# 1-Schematic_copilot.net
KiCad netlist of a schematic drawn in EasyEDA
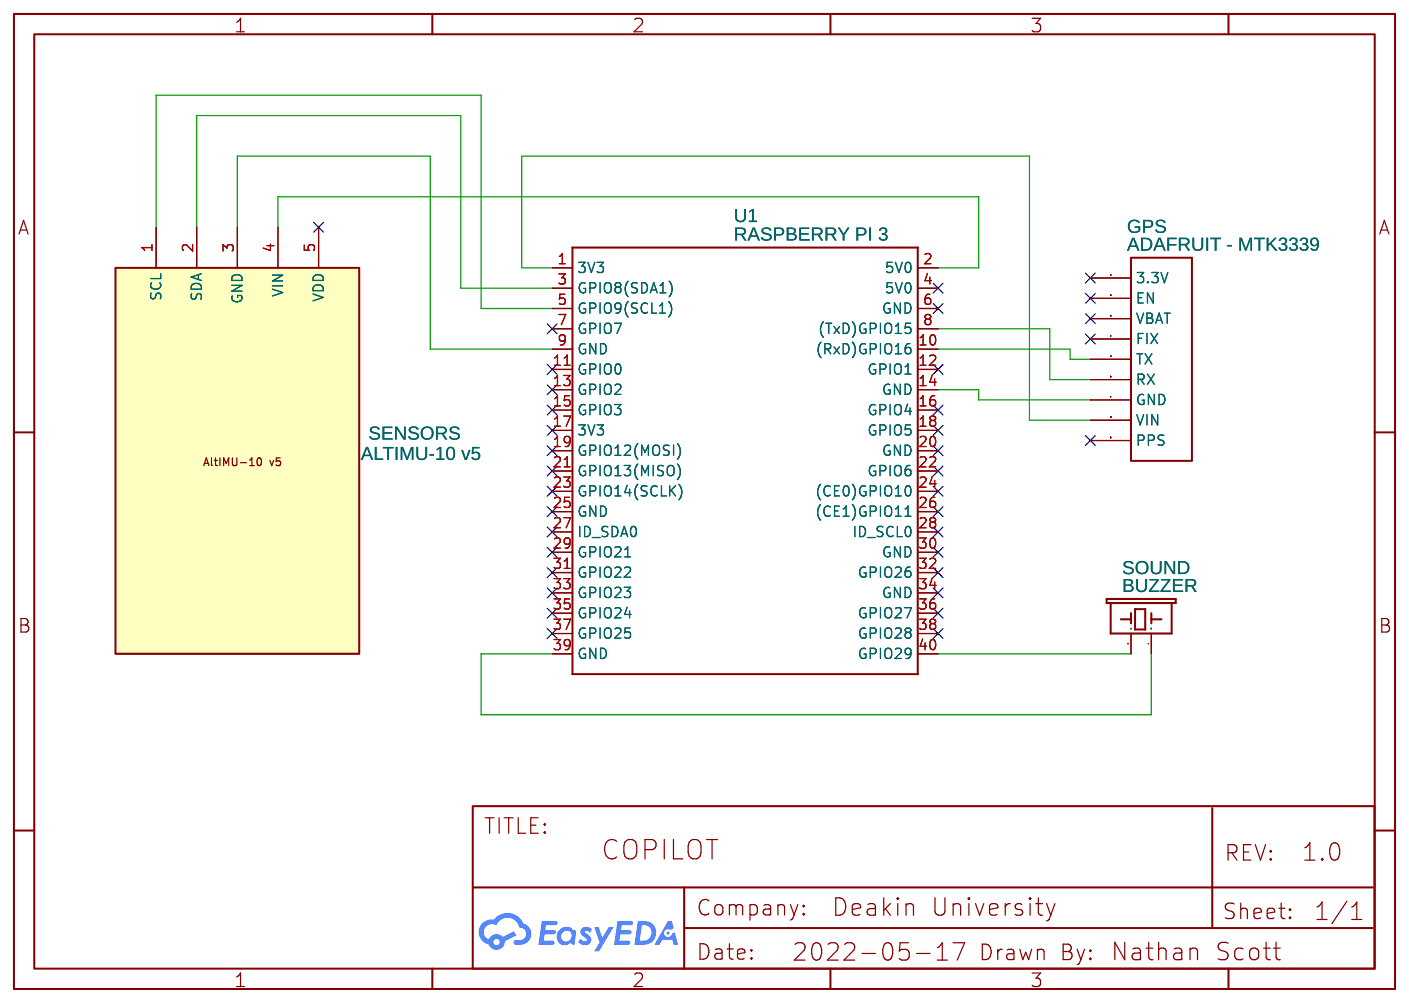
[diagram p0: copilot_sim]
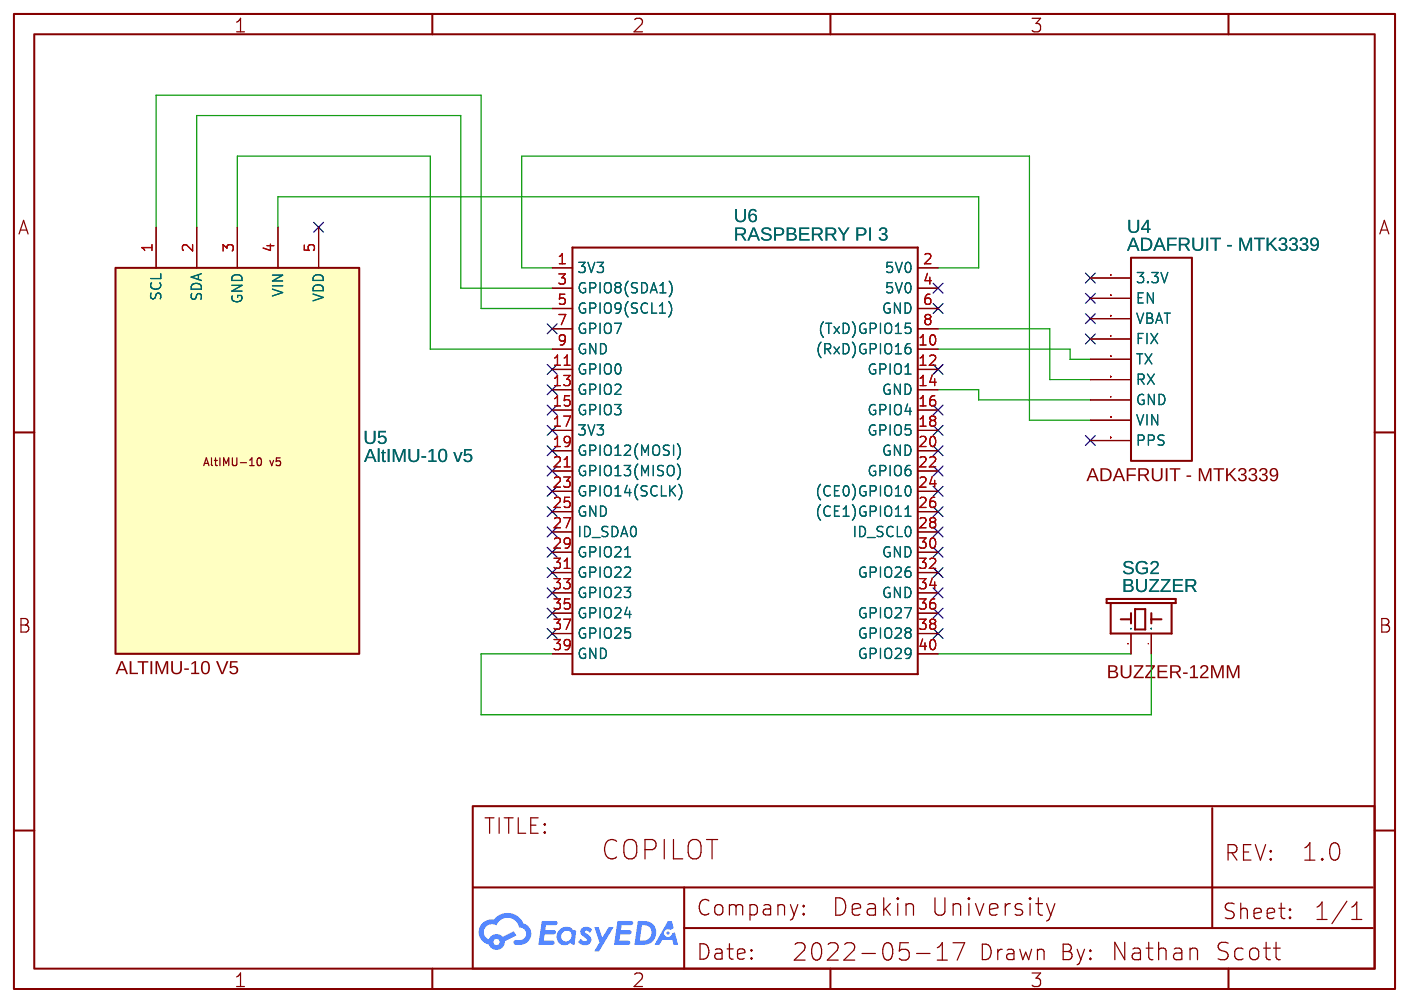
[diagram p1: copilot_sch]

(export (version "E")
  (design (tool "Eeschema 10.0.6"))
  (components
    (comp (ref "GPS") (value "ADAFRUIT - MTK3339") (libsource (lib "") (part "ADAFRUIT - MTK3339")))
    (comp (ref "SENSORS") (value "ALTIMU-10 v5") (libsource (lib "") (part "AltIMU-10 v5")))
    (comp (ref "SOUND") (value "BUZZER") (libsource (lib "") (part "BUZZER")))
    (comp (ref "U1")
      (value "RASPBERRY PI 3")
      (fields (field (name "BOM_Supplier Part") "RaspberryPi 3"))
      (libsource (lib "") (part "RASPBERRY PI 3"))
    )
    (comp (ref "SG2") (value "BUZZER") (libsource (lib "") (part "BUZZER")))
    (comp (ref "U4") (value "ADAFRUIT - MTK3339") (libsource (lib "") (part "ADAFRUIT - MTK3339")))
    (comp (ref "U5") (value "AltIMU-10 v5") (libsource (lib "") (part "AltIMU-10 v5")))
    (comp (ref "U6")
      (value "RASPBERRY PI 3")
      (fields (field (name "BOM_Supplier Part") "RaspberryPi 3"))
      (libsource (lib "") (part "RASPBERRY PI 3"))
    )
  )
  (nets
    (net (code "1") (name "Net-(GPS-GND)") (class "Default")
      (node (ref "GPS") (pin "7") (pinfunction "GND_7") (pintype "unspecified"))
      (node (ref "U1") (pin "14") (pinfunction "GND_14") (pintype "unspecified"))
    )
    (net (code "2") (name "Net-(GPS-RX)") (class "Default")
      (node (ref "GPS") (pin "6") (pinfunction "RX_6") (pintype "unspecified"))
      (node (ref "U1") (pin "8") (pinfunction "(TxD)GPIO15_8") (pintype "unspecified"))
    )
    (net (code "3") (name "Net-(GPS-TX)") (class "Default")
      (node (ref "GPS") (pin "5") (pinfunction "TX_5") (pintype "unspecified"))
      (node (ref "U1") (pin "10") (pinfunction "(RxD)GPIO16_10") (pintype "unspecified"))
    )
    (net (code "4") (name "Net-(GPS-VIN)") (class "Default")
      (node (ref "GPS") (pin "8") (pinfunction "VIN_8") (pintype "unspecified"))
      (node (ref "U1") (pin "1") (pinfunction "3V3_1") (pintype "unspecified"))
    )
    (net (code "5") (name "Net-(SENSORS-GND)") (class "Default")
      (node (ref "SENSORS") (pin "3") (pinfunction "GND_3") (pintype "unspecified"))
      (node (ref "U1") (pin "9") (pinfunction "GND_9") (pintype "unspecified"))
    )
    (net (code "6") (name "Net-(SENSORS-SCL)") (class "Default")
      (node (ref "SENSORS") (pin "1") (pinfunction "SCL_1") (pintype "unspecified"))
      (node (ref "U1") (pin "5") (pinfunction "GPIO9(SCL1)_5") (pintype "unspecified"))
    )
    (net (code "7") (name "Net-(SENSORS-SDA)") (class "Default")
      (node (ref "SENSORS") (pin "2") (pinfunction "SDA_2") (pintype "unspecified"))
      (node (ref "U1") (pin "3") (pinfunction "GPIO8(SDA1)_3") (pintype "unspecified"))
    )
    (net (code "8") (name "Net-(SENSORS-VIN)") (class "Default")
      (node (ref "SENSORS") (pin "4") (pinfunction "VIN_4") (pintype "unspecified"))
      (node (ref "U1") (pin "2") (pinfunction "5V0_2") (pintype "unspecified"))
    )
    (net (code "9") (name "Net-(SG2-1)") (class "Default")
      (node (ref "SG2") (pin "+") (pinfunction "1_+") (pintype "unspecified"))
      (node (ref "U6") (pin "40") (pinfunction "GPIO29_40") (pintype "unspecified"))
    )
    (net (code "10") (name "Net-(SG2-2)") (class "Default")
      (node (ref "SG2") (pin "-") (pinfunction "2_-") (pintype "unspecified"))
      (node (ref "U6") (pin "39") (pinfunction "GND_39") (pintype "unspecified"))
    )
    (net (code "11") (name "Net-(SOUND-1)") (class "Default")
      (node (ref "SOUND") (pin "+") (pinfunction "1_+") (pintype "unspecified"))
      (node (ref "U1") (pin "40") (pinfunction "GPIO29_40") (pintype "unspecified"))
    )
    (net (code "12") (name "Net-(SOUND-2)") (class "Default")
      (node (ref "SOUND") (pin "-") (pinfunction "2_-") (pintype "unspecified"))
      (node (ref "U1") (pin "39") (pinfunction "GND_39") (pintype "unspecified"))
    )
    (net (code "13") (name "Net-(U4-GND)") (class "Default")
      (node (ref "U4") (pin "7") (pinfunction "GND_7") (pintype "unspecified"))
      (node (ref "U6") (pin "14") (pinfunction "GND_14") (pintype "unspecified"))
    )
    (net (code "14") (name "Net-(U4-RX)") (class "Default")
      (node (ref "U4") (pin "6") (pinfunction "RX_6") (pintype "unspecified"))
      (node (ref "U6") (pin "8") (pinfunction "(TxD)GPIO15_8") (pintype "unspecified"))
    )
    (net (code "15") (name "Net-(U4-TX)") (class "Default")
      (node (ref "U4") (pin "5") (pinfunction "TX_5") (pintype "unspecified"))
      (node (ref "U6") (pin "10") (pinfunction "(RxD)GPIO16_10") (pintype "unspecified"))
    )
    (net (code "16") (name "Net-(U4-VIN)") (class "Default")
      (node (ref "U4") (pin "8") (pinfunction "VIN_8") (pintype "unspecified"))
      (node (ref "U6") (pin "1") (pinfunction "3V3_1") (pintype "unspecified"))
    )
    (net (code "17") (name "Net-(U5-GND)") (class "Default")
      (node (ref "U5") (pin "3") (pinfunction "GND_3") (pintype "unspecified"))
      (node (ref "U6") (pin "9") (pinfunction "GND_9") (pintype "unspecified"))
    )
    (net (code "18") (name "Net-(U5-SCL)") (class "Default")
      (node (ref "U5") (pin "1") (pinfunction "SCL_1") (pintype "unspecified"))
      (node (ref "U6") (pin "5") (pinfunction "GPIO9(SCL1)_5") (pintype "unspecified"))
    )
    (net (code "19") (name "Net-(U5-SDA)") (class "Default")
      (node (ref "U5") (pin "2") (pinfunction "SDA_2") (pintype "unspecified"))
      (node (ref "U6") (pin "3") (pinfunction "GPIO8(SDA1)_3") (pintype "unspecified"))
    )
    (net (code "20") (name "Net-(U5-VIN)") (class "Default")
      (node (ref "U5") (pin "4") (pinfunction "VIN_4") (pintype "unspecified"))
      (node (ref "U6") (pin "2") (pinfunction "5V0_2") (pintype "unspecified"))
    )
    (net (code "21") (name "unconnected-(GPS-3.3V-Pad1)") (class "Default")
      (node (ref "GPS") (pin "1") (pinfunction "3.3V_1") (pintype "unspecified+no_connect"))
    )
    (net (code "22") (name "unconnected-(GPS-EN-Pad2)") (class "Default")
      (node (ref "GPS") (pin "2") (pinfunction "EN_2") (pintype "unspecified+no_connect"))
    )
    (net (code "23") (name "unconnected-(GPS-FIX-Pad4)") (class "Default")
      (node (ref "GPS") (pin "4") (pinfunction "FIX_4") (pintype "unspecified+no_connect"))
    )
    (net (code "24") (name "unconnected-(GPS-PPS-Pad9)") (class "Default")
      (node (ref "GPS") (pin "9") (pinfunction "PPS_9") (pintype "unspecified+no_connect"))
    )
    (net (code "25") (name "unconnected-(GPS-VBAT-Pad3)") (class "Default")
      (node (ref "GPS") (pin "3") (pinfunction "VBAT_3") (pintype "unspecified+no_connect"))
    )
    (net (code "26") (name "unconnected-(SENSORS-VDD-Pad5)") (class "Default")
      (node (ref "SENSORS") (pin "5") (pinfunction "VDD_5") (pintype "unspecified+no_connect"))
    )
    (net (code "27") (name "unconnected-(U1-(CE0)GPIO10-Pad24)") (class "Default")
      (node (ref "U1") (pin "24") (pinfunction "(CE0)GPIO10_24") (pintype "unspecified+no_connect"))
    )
    (net (code "28") (name "unconnected-(U1-(CE1)GPIO11-Pad26)") (class "Default")
      (node (ref "U1") (pin "26") (pinfunction "(CE1)GPIO11_26") (pintype "unspecified+no_connect"))
    )
    (net (code "29") (name "unconnected-(U1-3V3-Pad17)") (class "Default")
      (node (ref "U1") (pin "17") (pinfunction "3V3_17") (pintype "unspecified+no_connect"))
    )
    (net (code "30") (name "unconnected-(U1-5V0-Pad4)") (class "Default")
      (node (ref "U1") (pin "4") (pinfunction "5V0_4") (pintype "unspecified+no_connect"))
    )
    (net (code "31") (name "unconnected-(U1-GND-Pad6)") (class "Default")
      (node (ref "U1") (pin "6") (pinfunction "GND_6") (pintype "unspecified+no_connect"))
    )
    (net (code "32") (name "unconnected-(U1-GND-Pad20)") (class "Default")
      (node (ref "U1") (pin "20") (pinfunction "GND_20") (pintype "unspecified+no_connect"))
    )
    (net (code "33") (name "unconnected-(U1-GND-Pad25)") (class "Default")
      (node (ref "U1") (pin "25") (pinfunction "GND_25") (pintype "unspecified+no_connect"))
    )
    (net (code "34") (name "unconnected-(U1-GND-Pad30)") (class "Default")
      (node (ref "U1") (pin "30") (pinfunction "GND_30") (pintype "unspecified+no_connect"))
    )
    (net (code "35") (name "unconnected-(U1-GND-Pad34)") (class "Default")
      (node (ref "U1") (pin "34") (pinfunction "GND_34") (pintype "unspecified+no_connect"))
    )
    (net (code "36") (name "unconnected-(U1-GPIO0-Pad11)") (class "Default")
      (node (ref "U1") (pin "11") (pinfunction "GPIO0_11") (pintype "unspecified+no_connect"))
    )
    (net (code "37") (name "unconnected-(U1-GPIO1-Pad12)") (class "Default")
      (node (ref "U1") (pin "12") (pinfunction "GPIO1_12") (pintype "unspecified+no_connect"))
    )
    (net (code "38") (name "unconnected-(U1-GPIO2-Pad13)") (class "Default")
      (node (ref "U1") (pin "13") (pinfunction "GPIO2_13") (pintype "unspecified+no_connect"))
    )
    (net (code "39") (name "unconnected-(U1-GPIO3-Pad15)") (class "Default")
      (node (ref "U1") (pin "15") (pinfunction "GPIO3_15") (pintype "unspecified+no_connect"))
    )
    (net (code "40") (name "unconnected-(U1-GPIO4-Pad16)") (class "Default")
      (node (ref "U1") (pin "16") (pinfunction "GPIO4_16") (pintype "unspecified+no_connect"))
    )
    (net (code "41") (name "unconnected-(U1-GPIO5-Pad18)") (class "Default")
      (node (ref "U1") (pin "18") (pinfunction "GPIO5_18") (pintype "unspecified+no_connect"))
    )
    (net (code "42") (name "unconnected-(U1-GPIO6-Pad22)") (class "Default")
      (node (ref "U1") (pin "22") (pinfunction "GPIO6_22") (pintype "unspecified+no_connect"))
    )
    (net (code "43") (name "unconnected-(U1-GPIO7-Pad7)") (class "Default")
      (node (ref "U1") (pin "7") (pinfunction "GPIO7_7") (pintype "unspecified+no_connect"))
    )
    (net (code "44") (name "unconnected-(U1-GPIO12(MOSI)-Pad19)") (class "Default")
      (node (ref "U1") (pin "19") (pinfunction "GPIO12(MOSI)_19") (pintype "unspecified+no_connect"))
    )
    (net (code "45") (name "unconnected-(U1-GPIO13(MISO)-Pad21)") (class "Default")
      (node (ref "U1") (pin "21") (pinfunction "GPIO13(MISO)_21") (pintype "unspecified+no_connect"))
    )
    (net (code "46") (name "unconnected-(U1-GPIO14(SCLK)-Pad23)") (class "Default")
      (node (ref "U1") (pin "23") (pinfunction "GPIO14(SCLK)_23") (pintype "unspecified+no_connect"))
    )
    (net (code "47") (name "unconnected-(U1-GPIO21-Pad29)") (class "Default")
      (node (ref "U1") (pin "29") (pinfunction "GPIO21_29") (pintype "unspecified+no_connect"))
    )
    (net (code "48") (name "unconnected-(U1-GPIO22-Pad31)") (class "Default")
      (node (ref "U1") (pin "31") (pinfunction "GPIO22_31") (pintype "unspecified+no_connect"))
    )
    (net (code "49") (name "unconnected-(U1-GPIO23-Pad33)") (class "Default")
      (node (ref "U1") (pin "33") (pinfunction "GPIO23_33") (pintype "unspecified+no_connect"))
    )
    (net (code "50") (name "unconnected-(U1-GPIO24-Pad35)") (class "Default")
      (node (ref "U1") (pin "35") (pinfunction "GPIO24_35") (pintype "unspecified+no_connect"))
    )
    (net (code "51") (name "unconnected-(U1-GPIO25-Pad37)") (class "Default")
      (node (ref "U1") (pin "37") (pinfunction "GPIO25_37") (pintype "unspecified+no_connect"))
    )
    (net (code "52") (name "unconnected-(U1-GPIO26-Pad32)") (class "Default")
      (node (ref "U1") (pin "32") (pinfunction "GPIO26_32") (pintype "unspecified+no_connect"))
    )
    (net (code "53") (name "unconnected-(U1-GPIO27-Pad36)") (class "Default")
      (node (ref "U1") (pin "36") (pinfunction "GPIO27_36") (pintype "unspecified+no_connect"))
    )
    (net (code "54") (name "unconnected-(U1-GPIO28-Pad38)") (class "Default")
      (node (ref "U1") (pin "38") (pinfunction "GPIO28_38") (pintype "unspecified+no_connect"))
    )
    (net (code "55") (name "unconnected-(U1-ID_SCL0-Pad28)") (class "Default")
      (node (ref "U1") (pin "28") (pinfunction "ID_SCL0_28") (pintype "unspecified+no_connect"))
    )
    (net (code "56") (name "unconnected-(U1-ID_SDA0-Pad27)") (class "Default")
      (node (ref "U1") (pin "27") (pinfunction "ID_SDA0_27") (pintype "unspecified+no_connect"))
    )
    (net (code "57") (name "unconnected-(U4-3.3V-Pad1)") (class "Default")
      (node (ref "U4") (pin "1") (pinfunction "3.3V_1") (pintype "unspecified+no_connect"))
    )
    (net (code "58") (name "unconnected-(U4-EN-Pad2)") (class "Default")
      (node (ref "U4") (pin "2") (pinfunction "EN_2") (pintype "unspecified+no_connect"))
    )
    (net (code "59") (name "unconnected-(U4-FIX-Pad4)") (class "Default")
      (node (ref "U4") (pin "4") (pinfunction "FIX_4") (pintype "unspecified+no_connect"))
    )
    (net (code "60") (name "unconnected-(U4-PPS-Pad9)") (class "Default")
      (node (ref "U4") (pin "9") (pinfunction "PPS_9") (pintype "unspecified+no_connect"))
    )
    (net (code "61") (name "unconnected-(U4-VBAT-Pad3)") (class "Default")
      (node (ref "U4") (pin "3") (pinfunction "VBAT_3") (pintype "unspecified+no_connect"))
    )
    (net (code "62") (name "unconnected-(U5-VDD-Pad5)") (class "Default")
      (node (ref "U5") (pin "5") (pinfunction "VDD_5") (pintype "unspecified+no_connect"))
    )
    (net (code "63") (name "unconnected-(U6-(CE0)GPIO10-Pad24)") (class "Default")
      (node (ref "U6") (pin "24") (pinfunction "(CE0)GPIO10_24") (pintype "unspecified+no_connect"))
    )
    (net (code "64") (name "unconnected-(U6-(CE1)GPIO11-Pad26)") (class "Default")
      (node (ref "U6") (pin "26") (pinfunction "(CE1)GPIO11_26") (pintype "unspecified+no_connect"))
    )
    (net (code "65") (name "unconnected-(U6-3V3-Pad17)") (class "Default")
      (node (ref "U6") (pin "17") (pinfunction "3V3_17") (pintype "unspecified+no_connect"))
    )
    (net (code "66") (name "unconnected-(U6-5V0-Pad4)") (class "Default")
      (node (ref "U6") (pin "4") (pinfunction "5V0_4") (pintype "unspecified+no_connect"))
    )
    (net (code "67") (name "unconnected-(U6-GND-Pad6)") (class "Default")
      (node (ref "U6") (pin "6") (pinfunction "GND_6") (pintype "unspecified+no_connect"))
    )
    (net (code "68") (name "unconnected-(U6-GND-Pad20)") (class "Default")
      (node (ref "U6") (pin "20") (pinfunction "GND_20") (pintype "unspecified+no_connect"))
    )
    (net (code "69") (name "unconnected-(U6-GND-Pad25)") (class "Default")
      (node (ref "U6") (pin "25") (pinfunction "GND_25") (pintype "unspecified+no_connect"))
    )
    (net (code "70") (name "unconnected-(U6-GND-Pad30)") (class "Default")
      (node (ref "U6") (pin "30") (pinfunction "GND_30") (pintype "unspecified+no_connect"))
    )
    (net (code "71") (name "unconnected-(U6-GND-Pad34)") (class "Default")
      (node (ref "U6") (pin "34") (pinfunction "GND_34") (pintype "unspecified+no_connect"))
    )
    (net (code "72") (name "unconnected-(U6-GPIO0-Pad11)") (class "Default")
      (node (ref "U6") (pin "11") (pinfunction "GPIO0_11") (pintype "unspecified+no_connect"))
    )
    (net (code "73") (name "unconnected-(U6-GPIO1-Pad12)") (class "Default")
      (node (ref "U6") (pin "12") (pinfunction "GPIO1_12") (pintype "unspecified+no_connect"))
    )
    (net (code "74") (name "unconnected-(U6-GPIO2-Pad13)") (class "Default")
      (node (ref "U6") (pin "13") (pinfunction "GPIO2_13") (pintype "unspecified+no_connect"))
    )
    (net (code "75") (name "unconnected-(U6-GPIO3-Pad15)") (class "Default")
      (node (ref "U6") (pin "15") (pinfunction "GPIO3_15") (pintype "unspecified+no_connect"))
    )
    (net (code "76") (name "unconnected-(U6-GPIO4-Pad16)") (class "Default")
      (node (ref "U6") (pin "16") (pinfunction "GPIO4_16") (pintype "unspecified+no_connect"))
    )
    (net (code "77") (name "unconnected-(U6-GPIO5-Pad18)") (class "Default")
      (node (ref "U6") (pin "18") (pinfunction "GPIO5_18") (pintype "unspecified+no_connect"))
    )
    (net (code "78") (name "unconnected-(U6-GPIO6-Pad22)") (class "Default")
      (node (ref "U6") (pin "22") (pinfunction "GPIO6_22") (pintype "unspecified+no_connect"))
    )
    (net (code "79") (name "unconnected-(U6-GPIO7-Pad7)") (class "Default")
      (node (ref "U6") (pin "7") (pinfunction "GPIO7_7") (pintype "unspecified+no_connect"))
    )
    (net (code "80") (name "unconnected-(U6-GPIO12(MOSI)-Pad19)") (class "Default")
      (node (ref "U6") (pin "19") (pinfunction "GPIO12(MOSI)_19") (pintype "unspecified+no_connect"))
    )
    (net (code "81") (name "unconnected-(U6-GPIO13(MISO)-Pad21)") (class "Default")
      (node (ref "U6") (pin "21") (pinfunction "GPIO13(MISO)_21") (pintype "unspecified+no_connect"))
    )
    (net (code "82") (name "unconnected-(U6-GPIO14(SCLK)-Pad23)") (class "Default")
      (node (ref "U6") (pin "23") (pinfunction "GPIO14(SCLK)_23") (pintype "unspecified+no_connect"))
    )
    (net (code "83") (name "unconnected-(U6-GPIO21-Pad29)") (class "Default")
      (node (ref "U6") (pin "29") (pinfunction "GPIO21_29") (pintype "unspecified+no_connect"))
    )
    (net (code "84") (name "unconnected-(U6-GPIO22-Pad31)") (class "Default")
      (node (ref "U6") (pin "31") (pinfunction "GPIO22_31") (pintype "unspecified+no_connect"))
    )
    (net (code "85") (name "unconnected-(U6-GPIO23-Pad33)") (class "Default")
      (node (ref "U6") (pin "33") (pinfunction "GPIO23_33") (pintype "unspecified+no_connect"))
    )
    (net (code "86") (name "unconnected-(U6-GPIO24-Pad35)") (class "Default")
      (node (ref "U6") (pin "35") (pinfunction "GPIO24_35") (pintype "unspecified+no_connect"))
    )
    (net (code "87") (name "unconnected-(U6-GPIO25-Pad37)") (class "Default")
      (node (ref "U6") (pin "37") (pinfunction "GPIO25_37") (pintype "unspecified+no_connect"))
    )
    (net (code "88") (name "unconnected-(U6-GPIO26-Pad32)") (class "Default")
      (node (ref "U6") (pin "32") (pinfunction "GPIO26_32") (pintype "unspecified+no_connect"))
    )
    (net (code "89") (name "unconnected-(U6-GPIO27-Pad36)") (class "Default")
      (node (ref "U6") (pin "36") (pinfunction "GPIO27_36") (pintype "unspecified+no_connect"))
    )
    (net (code "90") (name "unconnected-(U6-GPIO28-Pad38)") (class "Default")
      (node (ref "U6") (pin "38") (pinfunction "GPIO28_38") (pintype "unspecified+no_connect"))
    )
    (net (code "91") (name "unconnected-(U6-ID_SCL0-Pad28)") (class "Default")
      (node (ref "U6") (pin "28") (pinfunction "ID_SCL0_28") (pintype "unspecified+no_connect"))
    )
    (net (code "92") (name "unconnected-(U6-ID_SDA0-Pad27)") (class "Default")
      (node (ref "U6") (pin "27") (pinfunction "ID_SDA0_27") (pintype "unspecified+no_connect"))
    )
  )
)
